# LuxLogger_V2_sensors.net
KiCad netlist of a schematic drawn in Altium Designer
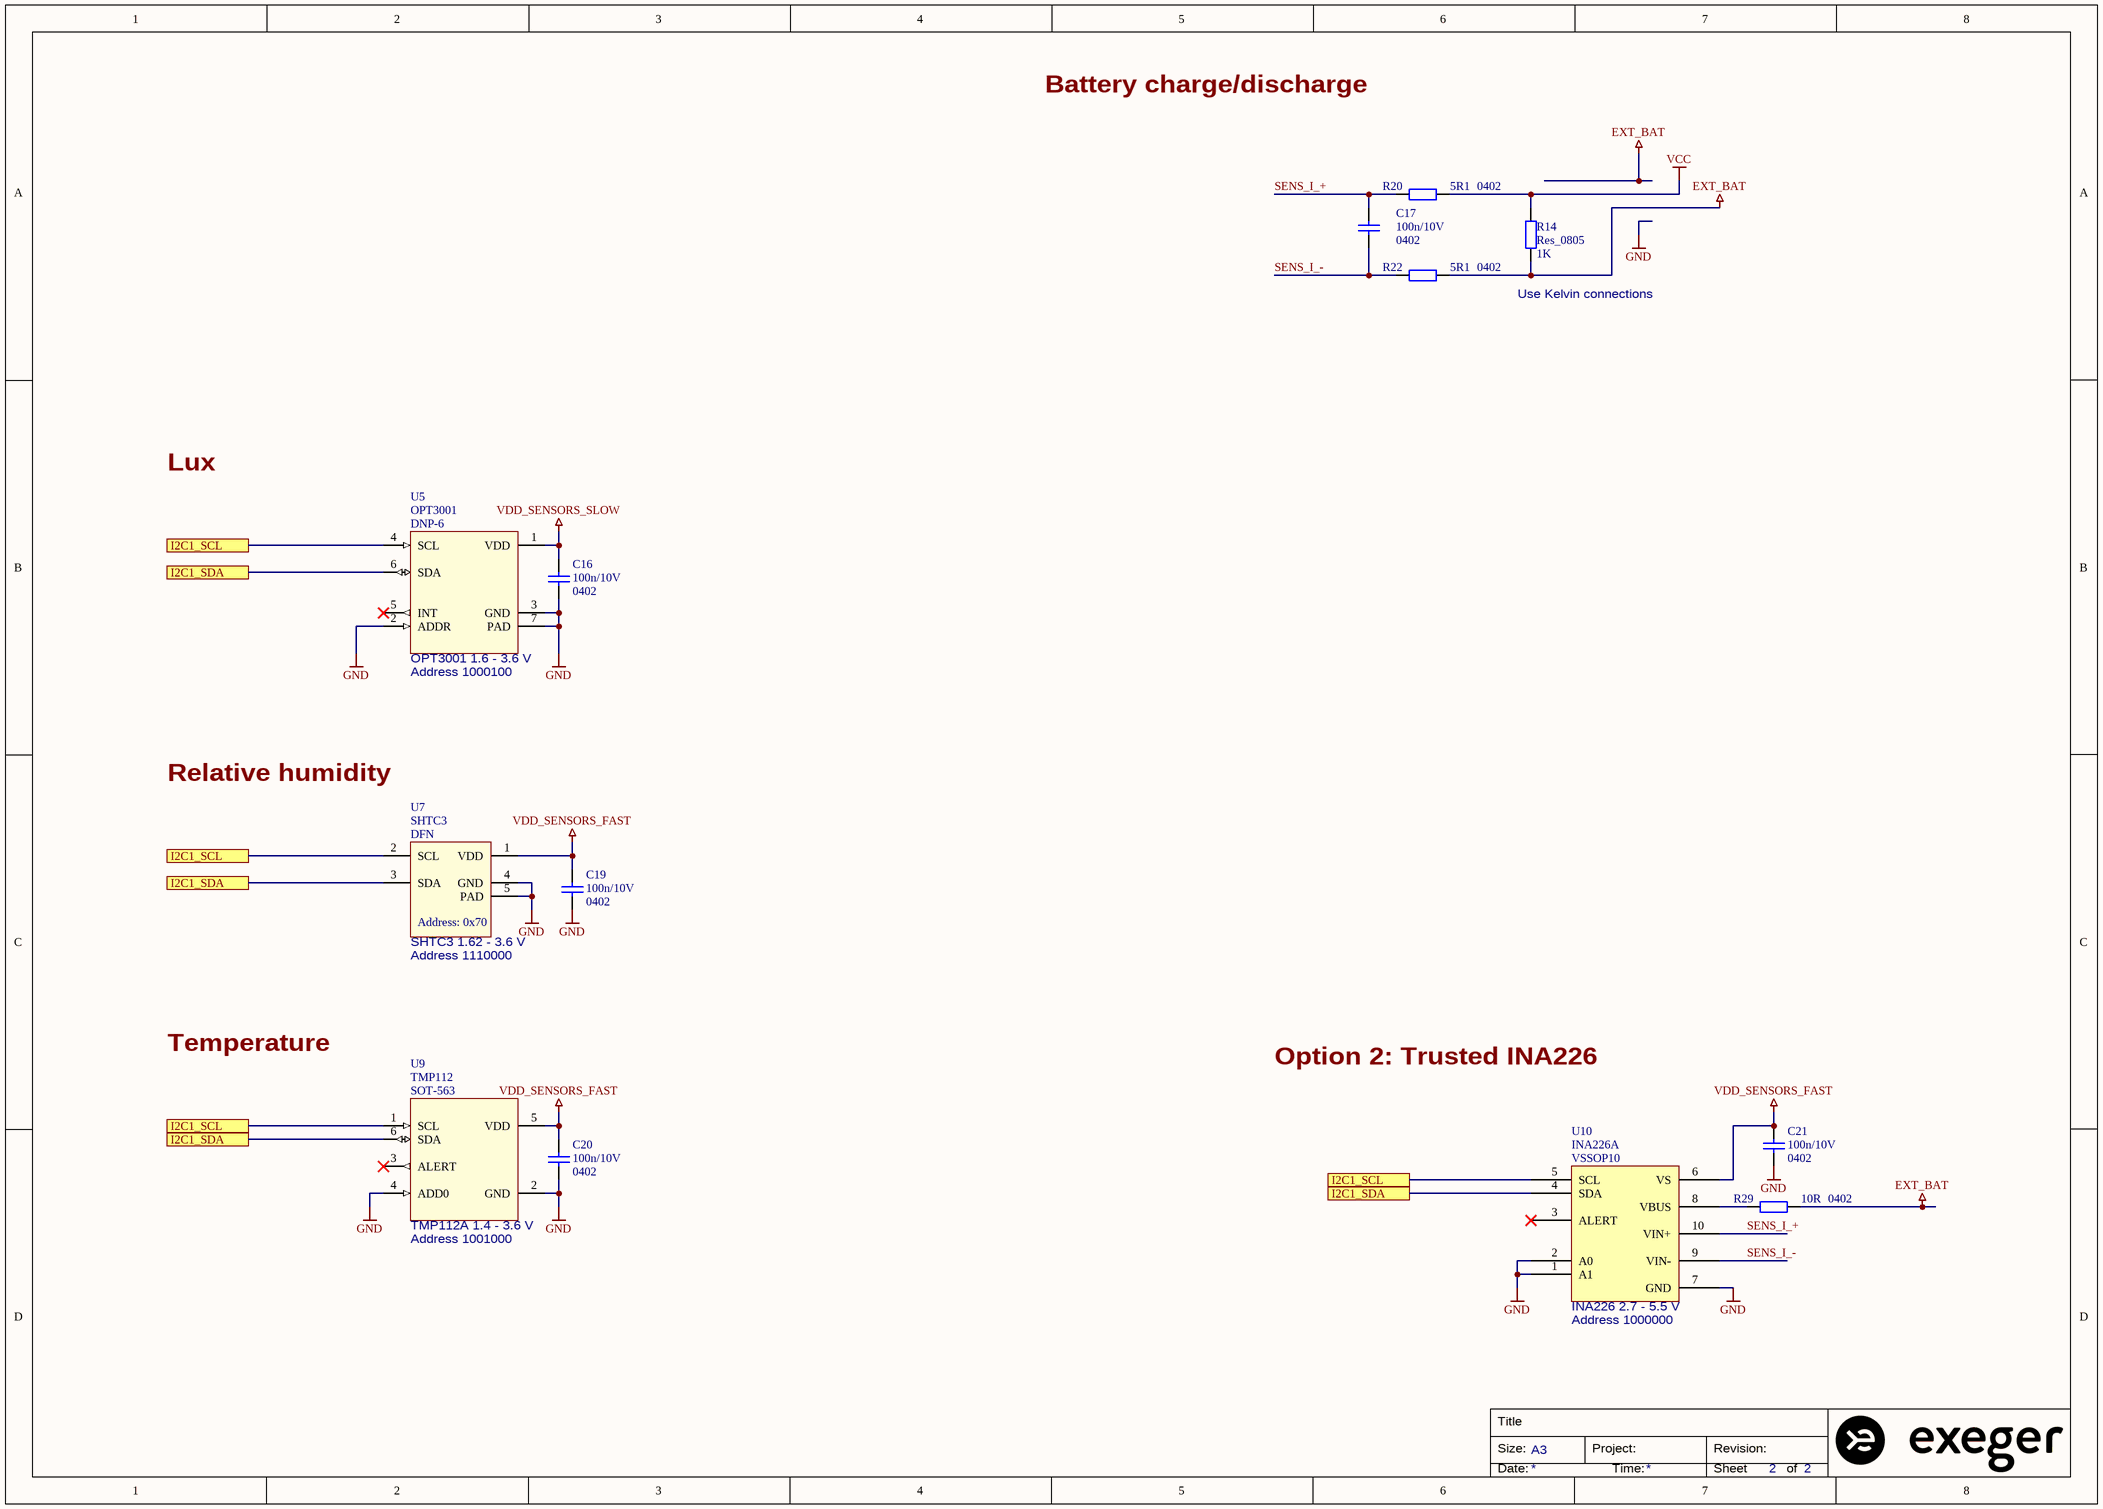
[diagram p0: LuxLogger_V2_sensors.SchDoc]

(export (version "E")
  (design (tool "Eeschema 10.0.6"))
  (components
    (comp (ref "C16")
      (value "~")
      (footprint "CAP0402")
      (description "Capacitor")
      (fields (field (name "SPECIFICATION") "100n/10V") (field (name "PACKAGE") "0402"))
      (libsource (lib "Miscellaneous Devices") (part "Cap"))
    )
    (comp (ref "C17")
      (value "~")
      (footprint "CAP0402")
      (description "Capacitor")
      (fields (field (name "SPECIFICATION") "100n/10V") (field (name "PACKAGE") "0402"))
      (libsource (lib "Miscellaneous Devices") (part "Cap"))
    )
    (comp (ref "C19")
      (value "~")
      (footprint "CAP0402")
      (description "Capacitor")
      (fields (field (name "SPECIFICATION") "100n/10V") (field (name "PACKAGE") "0402"))
      (libsource (lib "Miscellaneous Devices") (part "Cap"))
    )
    (comp (ref "C20")
      (value "~")
      (footprint "CAP0402")
      (description "Capacitor")
      (fields (field (name "SPECIFICATION") "100n/10V") (field (name "PACKAGE") "0402"))
      (libsource (lib "Miscellaneous Devices") (part "Cap"))
    )
    (comp (ref "C21")
      (value "~")
      (footprint "CAP0402")
      (description "Capacitor")
      (fields (field (name "SPECIFICATION") "100n/10V") (field (name "PACKAGE") "0402"))
      (libsource (lib "Miscellaneous Devices") (part "Cap"))
    )
    (comp (ref "R14")
      (value "Res_0805")
      (footprint "0805")
      (description "Resistor")
      (fields (field (name "ALTIUM_VALUE") "1K") (field (name "PUBLISHER") "Altium Limited"))
      (libsource (lib "Schematic_Components") (part "Res_0805"))
    )
    (comp (ref "R20")
      (value "~")
      (footprint "RES0402")
      (description "Resistor")
      (fields (field (name "PACKAGE") "0402") (field (name "SPECIFICATION") "5R1"))
      (libsource (lib "Miscellaneous Devices") (part "Res2"))
    )
    (comp (ref "R22")
      (value "~")
      (footprint "RES0402")
      (description "Resistor")
      (fields (field (name "PACKAGE") "0402") (field (name "SPECIFICATION") "5R1"))
      (libsource (lib "Miscellaneous Devices") (part "Res2"))
    )
    (comp (ref "R29")
      (value "~")
      (footprint "RES0402")
      (description "Resistor")
      (fields (field (name "PACKAGE") "0402") (field (name "SPECIFICATION") "10R"))
      (libsource (lib "Miscellaneous Devices") (part "Res2"))
    )
    (comp (ref "U5")
      (value "~")
      (footprint "OPT3001")
      (description "Lux sensor")
      (fields
        (field (name "MANUFACTURER") "TI")
        (field (name "SPECIFICATION") "OPT3001")
        (field (name "PACKAGE") "DNP-6")
      )
      (libsource (lib "Exeger_schematic_library") (part "OPT3001"))
    )
    (comp (ref "U7")
      (value "~")
      (footprint "SHTC3")
      (description "SHTC3 RH sensor")
      (fields
        (field (name "MANUFACTURER") "SENSIRION")
        (field (name "SPECIFICATION") "SHTC3")
        (field (name "PACKAGE") "DFN")
      )
      (libsource (lib "Exeger_schematic_library") (part "SHTC3"))
    )
    (comp (ref "U9")
      (value "~")
      (footprint "SOTFL50P160X60-6N")
      (description "Temp_Sensor")
      (fields
        (field (name "PACKAGE") "SOT-563")
        (field (name "SPECIFICATION") "TMP112")
        (field (name "MANUFACTURER") "TI")
      )
      (libsource (lib "Exeger_schematic_library") (part "TMP112A"))
    )
    (comp (ref "U10")
      (value "~")
      (footprint "VSSOP-10")
      (description "Current and power monitor")
      (fields
        (field (name "MANUFACTURER") "TI")
        (field (name "PACKAGE") "VSSOP10")
        (field (name "SPECIFICATION") "INA226A")
      )
      (libsource (lib "Exeger_schematic_library") (part "INA226"))
    )
  )
  (nets
    (net (code "1") (name "/I2C1_SCL") (class "Default")
      (node (ref "U10") (pin "5") (pinfunction "SCL_5") (pintype "passive"))
      (node (ref "U5") (pin "4") (pinfunction "SCL_4") (pintype "input"))
      (node (ref "U7") (pin "2") (pinfunction "SCL_2") (pintype "passive"))
      (node (ref "U9") (pin "1") (pinfunction "SCL_1") (pintype "input"))
    )
    (net (code "2") (name "/I2C1_SDA") (class "Default")
      (node (ref "U10") (pin "4") (pinfunction "SDA_4") (pintype "passive"))
      (node (ref "U5") (pin "6") (pinfunction "SDA_6") (pintype "bidirectional"))
      (node (ref "U7") (pin "3") (pinfunction "SDA_3") (pintype "passive"))
      (node (ref "U9") (pin "6") (pinfunction "SDA_6") (pintype "bidirectional"))
    )
    (net (code "3") (name "/SENS_I_+") (class "Default")
      (node (ref "C17") (pin "2") (pinfunction "2_2") (pintype "passive"))
      (node (ref "R20") (pin "2") (pinfunction "2_2") (pintype "passive"))
      (node (ref "U10") (pin "10") (pinfunction "VIN+_10") (pintype "passive"))
    )
    (net (code "4") (name "/SENS_I_-") (class "Default")
      (node (ref "C17") (pin "1") (pinfunction "1_1") (pintype "passive"))
      (node (ref "R22") (pin "2") (pinfunction "2_2") (pintype "passive"))
      (node (ref "U10") (pin "9") (pinfunction "VIN-_9") (pintype "passive"))
    )
    (net (code "5") (name "EXT_BAT") (class "Default")
      (node (ref "R14") (pin "1") (pinfunction "1_1") (pintype "passive"))
      (node (ref "R22") (pin "1") (pinfunction "1_1") (pintype "passive"))
      (node (ref "R29") (pin "1") (pinfunction "1_1") (pintype "passive"))
    )
    (net (code "6") (name "GND") (class "Default")
      (node (ref "C16") (pin "1") (pinfunction "1_1") (pintype "passive"))
      (node (ref "C19") (pin "1") (pinfunction "1_1") (pintype "passive"))
      (node (ref "C20") (pin "1") (pinfunction "1_1") (pintype "passive"))
      (node (ref "C21") (pin "1") (pinfunction "1_1") (pintype "passive"))
      (node (ref "U10") (pin "1") (pinfunction "A1_1") (pintype "passive"))
      (node (ref "U10") (pin "2") (pinfunction "A0_2") (pintype "passive"))
      (node (ref "U10") (pin "7") (pinfunction "GND_7") (pintype "passive"))
      (node (ref "U5") (pin "2") (pinfunction "ADDR_2") (pintype "input"))
      (node (ref "U5") (pin "3") (pinfunction "GND_3") (pintype "power_in"))
      (node (ref "U5") (pin "7") (pinfunction "PAD_7") (pintype "power_in"))
      (node (ref "U7") (pin "4") (pinfunction "GND_4") (pintype "passive"))
      (node (ref "U7") (pin "5") (pinfunction "PAD_5") (pintype "passive"))
      (node (ref "U9") (pin "2") (pinfunction "GND_2") (pintype "power_in"))
      (node (ref "U9") (pin "4") (pinfunction "ADD0_4") (pintype "input"))
    )
    (net (code "7") (name "Net-(U10-VBUS)") (class "Default")
      (node (ref "R29") (pin "2") (pinfunction "2_2") (pintype "passive"))
      (node (ref "U10") (pin "8") (pinfunction "VBUS_8") (pintype "passive"))
    )
    (net (code "8") (name "VCC") (class "Default")
      (node (ref "R14") (pin "2") (pinfunction "2_2") (pintype "passive"))
      (node (ref "R20") (pin "1") (pinfunction "1_1") (pintype "passive"))
    )
    (net (code "9") (name "VDD_SENSORS_FAST") (class "Default")
      (node (ref "C19") (pin "2") (pinfunction "2_2") (pintype "passive"))
      (node (ref "C20") (pin "2") (pinfunction "2_2") (pintype "passive"))
      (node (ref "C21") (pin "2") (pinfunction "2_2") (pintype "passive"))
      (node (ref "U10") (pin "6") (pinfunction "VS_6") (pintype "passive"))
      (node (ref "U7") (pin "1") (pinfunction "VDD_1") (pintype "passive"))
      (node (ref "U9") (pin "5") (pinfunction "VDD_5") (pintype "power_in"))
    )
    (net (code "10") (name "VDD_SENSORS_SLOW") (class "Default")
      (node (ref "C16") (pin "2") (pinfunction "2_2") (pintype "passive"))
      (node (ref "U5") (pin "1") (pinfunction "VDD_1") (pintype "power_in"))
    )
    (net (code "11") (name "unconnected-(U5-INT-Pad5)") (class "Default")
      (node (ref "U5") (pin "5") (pinfunction "INT_5") (pintype "output+no_connect"))
    )
    (net (code "12") (name "unconnected-(U9-ALERT-Pad3)") (class "Default")
      (node (ref "U9") (pin "3") (pinfunction "ALERT_3") (pintype "output+no_connect"))
    )
    (net (code "13") (name "unconnected-(U10-ALERT-Pad3)") (class "Default")
      (node (ref "U10") (pin "3") (pinfunction "ALERT_3") (pintype "passive+no_connect"))
    )
  )
)
